# Phase_Voltage_Dividers.net
KiCad netlist of a schematic drawn in Altium Designer
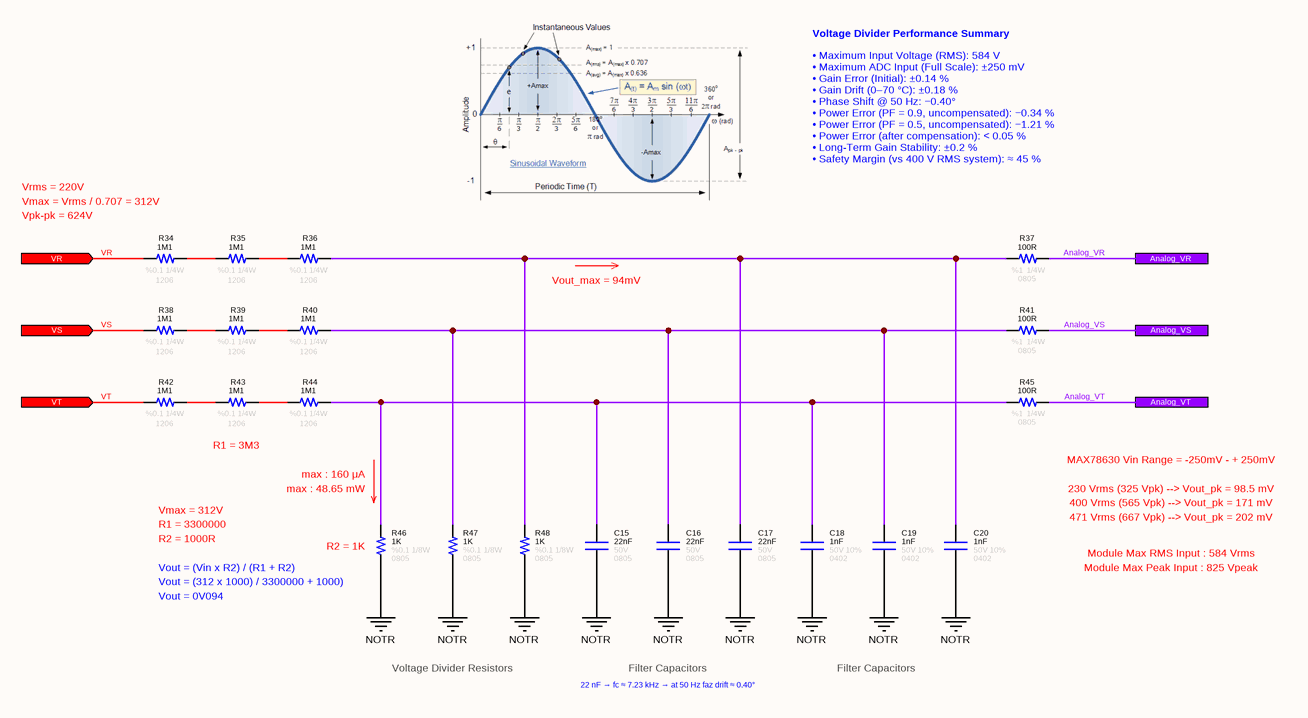
[diagram p0: Phase Voltage Dividers.SchDoc]

(export (version "E")
  (design (tool "Eeschema 10.0.6"))
  (components
    (comp (ref "C15")
      (value "22nF")
      (footprint "CAPACITOR_0805")
      (description "Capacitor (MLCC) - 22nF / 50V / 0805")
      (fields
        (field (name "MANUFACTURER PART NUMBER") "C0805C223K5RACTU")
        (field (name "TOLERANCE") "10%")
        (field (name "CASE") "0805")
        (field (name "VOLTAGE") "50V")
      )
      (libsource (lib "Akkoyun") (part "Capacitor - 22nF [0805-50V]"))
    )
    (comp (ref "C16")
      (value "22nF")
      (footprint "CAPACITOR_0805")
      (description "Capacitor (MLCC) - 22nF / 50V / 0805")
      (fields
        (field (name "MANUFACTURER PART NUMBER") "C0805C223K5RACTU")
        (field (name "TOLERANCE") "10%")
        (field (name "CASE") "0805")
        (field (name "VOLTAGE") "50V")
      )
      (libsource (lib "Akkoyun") (part "Capacitor - 22nF [0805-50V]"))
    )
    (comp (ref "C17")
      (value "22nF")
      (footprint "CAPACITOR_0805")
      (description "Capacitor (MLCC) - 22nF / 50V / 0805")
      (fields
        (field (name "MANUFACTURER PART NUMBER") "C0805C223K5RACTU")
        (field (name "TOLERANCE") "10%")
        (field (name "CASE") "0805")
        (field (name "VOLTAGE") "50V")
      )
      (libsource (lib "Akkoyun") (part "Capacitor - 22nF [0805-50V]"))
    )
    (comp (ref "C18")
      (value "1nF")
      (footprint "CAPACITOR_0402")
      (description "Capacitor (MLCC) - 1nF / 50V / 0402")
      (fields
        (field (name "MANUFACTURER PART NUMBER") "GRM155R71H102KA01D")
        (field (name "TOLERANCE") "10%")
        (field (name "CASE") "0402")
        (field (name "VOLTAGE") "50V")
        (field (name "Comment") "Capacitor - 1nF [0402] (MLCC)")
      )
      (libsource (lib "Akkoyun") (part "Capacitor - 1nF [0402-50V]"))
    )
    (comp (ref "C19")
      (value "1nF")
      (footprint "CAPACITOR_0402")
      (description "Capacitor (MLCC) - 1nF / 50V / 0402")
      (fields
        (field (name "MANUFACTURER PART NUMBER") "GRM155R71H102KA01D")
        (field (name "TOLERANCE") "10%")
        (field (name "CASE") "0402")
        (field (name "VOLTAGE") "50V")
        (field (name "Comment") "Capacitor - 1nF [0402] (MLCC)")
      )
      (libsource (lib "Akkoyun") (part "Capacitor - 1nF [0402-50V]"))
    )
    (comp (ref "C20")
      (value "1nF")
      (footprint "CAPACITOR_0402")
      (description "Capacitor (MLCC) - 1nF / 50V / 0402")
      (fields
        (field (name "MANUFACTURER PART NUMBER") "GRM155R71H102KA01D")
        (field (name "TOLERANCE") "10%")
        (field (name "CASE") "0402")
        (field (name "VOLTAGE") "50V")
        (field (name "Comment") "Capacitor - 1nF [0402] (MLCC)")
      )
      (libsource (lib "Akkoyun") (part "Capacitor - 1nF [0402-50V]"))
    )
    (comp (ref "R34")
      (value "1M1")
      (footprint "RESISTOR_1206")
      (description "Thick Film Resistors - SMD 1/4 W 1.1 MOhm 0.1%")
      (fields
        (field (name "MANUFACTURER PART NUMBER") "RT1206BRD071M1L")
        (field (name "CASE") "1206")
        (field (name "TOLERANCE") "%0.1")
        (field (name "POWER") "1/4W")
        (field (name "Comment") "1M1 - 1206 - %1 - 1/4W")
      )
      (libsource (lib "Akkoyun") (part "Resistor - 1M1 [1206] %0.1"))
    )
    (comp (ref "R35")
      (value "1M1")
      (footprint "RESISTOR_1206")
      (description "Thick Film Resistors - SMD 1/4 W 1.1 MOhm 0.1%")
      (fields
        (field (name "MANUFACTURER PART NUMBER") "RT1206BRD071M1L")
        (field (name "CASE") "1206")
        (field (name "TOLERANCE") "%0.1")
        (field (name "POWER") "1/4W")
        (field (name "Comment") "1M1 - 1206 - %1 - 1/4W")
      )
      (libsource (lib "Akkoyun") (part "Resistor - 1M1 [1206] %0.1"))
    )
    (comp (ref "R36")
      (value "1M1")
      (footprint "RESISTOR_1206")
      (description "Thick Film Resistors - SMD 1/4 W 1.1 MOhm 0.1%")
      (fields
        (field (name "MANUFACTURER PART NUMBER") "RT1206BRD071M1L")
        (field (name "CASE") "1206")
        (field (name "TOLERANCE") "%0.1")
        (field (name "POWER") "1/4W")
        (field (name "Comment") "1M1 - 1206 - %1 - 1/4W")
      )
      (libsource (lib "Akkoyun") (part "Resistor - 1M1 [1206] %0.1"))
    )
    (comp (ref "R37")
      (value "100R")
      (footprint "RESISTOR_0805")
      (description "Thick Film Resistors - SMD 1/4 W 100 Ohm 1%")
      (fields
        (field (name "MANUFACTURER PART NUMBER") "CRCW0805100RFKEA")
        (field (name "CASE") "0805")
        (field (name "TOLERANCE") "%1")
        (field (name "POWER") "1/4W")
        (field (name "Comment") "100R - 0805 - %1 - 1/4W")
      )
      (libsource (lib "Akkoyun") (part "Resistor - 100R [0805]"))
    )
    (comp (ref "R38")
      (value "1M1")
      (footprint "RESISTOR_1206")
      (description "Thick Film Resistors - SMD 1/4 W 1.1 MOhm 0.1%")
      (fields
        (field (name "MANUFACTURER PART NUMBER") "RT1206BRD071M1L")
        (field (name "CASE") "1206")
        (field (name "TOLERANCE") "%0.1")
        (field (name "POWER") "1/4W")
        (field (name "Comment") "1M1 - 1206 - %1 - 1/4W")
      )
      (libsource (lib "Akkoyun") (part "Resistor - 1M1 [1206] %0.1"))
    )
    (comp (ref "R39")
      (value "1M1")
      (footprint "RESISTOR_1206")
      (description "Thick Film Resistors - SMD 1/4 W 1.1 MOhm 0.1%")
      (fields
        (field (name "MANUFACTURER PART NUMBER") "RT1206BRD071M1L")
        (field (name "CASE") "1206")
        (field (name "TOLERANCE") "%0.1")
        (field (name "POWER") "1/4W")
        (field (name "Comment") "1M1 - 1206 - %1 - 1/4W")
      )
      (libsource (lib "Akkoyun") (part "Resistor - 1M1 [1206] %0.1"))
    )
    (comp (ref "R40")
      (value "1M1")
      (footprint "RESISTOR_1206")
      (description "Thick Film Resistors - SMD 1/4 W 1.1 MOhm 0.1%")
      (fields
        (field (name "MANUFACTURER PART NUMBER") "RT1206BRD071M1L")
        (field (name "CASE") "1206")
        (field (name "TOLERANCE") "%0.1")
        (field (name "POWER") "1/4W")
        (field (name "Comment") "1M1 - 1206 - %1 - 1/4W")
      )
      (libsource (lib "Akkoyun") (part "Resistor - 1M1 [1206] %0.1"))
    )
    (comp (ref "R41")
      (value "100R")
      (footprint "RESISTOR_0805")
      (description "Thick Film Resistors - SMD 1/4 W 100 Ohm 1%")
      (fields
        (field (name "MANUFACTURER PART NUMBER") "CRCW0805100RFKEA")
        (field (name "CASE") "0805")
        (field (name "TOLERANCE") "%1")
        (field (name "POWER") "1/4W")
        (field (name "Comment") "100R - 0805 - %1 - 1/4W")
      )
      (libsource (lib "Akkoyun") (part "Resistor - 100R [0805]"))
    )
    (comp (ref "R42")
      (value "1M1")
      (footprint "RESISTOR_1206")
      (description "Thick Film Resistors - SMD 1/4 W 1.1 MOhm 0.1%")
      (fields
        (field (name "MANUFACTURER PART NUMBER") "RT1206BRD071M1L")
        (field (name "CASE") "1206")
        (field (name "TOLERANCE") "%0.1")
        (field (name "POWER") "1/4W")
        (field (name "Comment") "1M1 - 1206 - %1 - 1/4W")
      )
      (libsource (lib "Akkoyun") (part "Resistor - 1M1 [1206] %0.1"))
    )
    (comp (ref "R43")
      (value "1M1")
      (footprint "RESISTOR_1206")
      (description "Thick Film Resistors - SMD 1/4 W 1.1 MOhm 0.1%")
      (fields
        (field (name "MANUFACTURER PART NUMBER") "RT1206BRD071M1L")
        (field (name "CASE") "1206")
        (field (name "TOLERANCE") "%0.1")
        (field (name "POWER") "1/4W")
        (field (name "Comment") "1M1 - 1206 - %1 - 1/4W")
      )
      (libsource (lib "Akkoyun") (part "Resistor - 1M1 [1206] %0.1"))
    )
    (comp (ref "R44")
      (value "1M1")
      (footprint "RESISTOR_1206")
      (description "Thick Film Resistors - SMD 1/4 W 1.1 MOhm 0.1%")
      (fields
        (field (name "MANUFACTURER PART NUMBER") "RT1206BRD071M1L")
        (field (name "CASE") "1206")
        (field (name "TOLERANCE") "%0.1")
        (field (name "POWER") "1/4W")
        (field (name "Comment") "1M1 - 1206 - %1 - 1/4W")
      )
      (libsource (lib "Akkoyun") (part "Resistor - 1M1 [1206] %0.1"))
    )
    (comp (ref "R45")
      (value "100R")
      (footprint "RESISTOR_0805")
      (description "Thick Film Resistors - SMD 1/4 W 100 Ohm 1%")
      (fields
        (field (name "MANUFACTURER PART NUMBER") "CRCW0805100RFKEA")
        (field (name "CASE") "0805")
        (field (name "TOLERANCE") "%1")
        (field (name "POWER") "1/4W")
        (field (name "Comment") "100R - 0805 - %1 - 1/4W")
      )
      (libsource (lib "Akkoyun") (part "Resistor - 100R [0805]"))
    )
    (comp (ref "R46")
      (value "1K")
      (footprint "RESISTOR_0805")
      (description "Thick Film Resistors - SMD 1/8 W 1 KOhm 0.1%")
      (fields
        (field (name "MANUFACTURER PART NUMBER") "ERA-6AEB102V")
        (field (name "TOLERANCE") "%0.1")
        (field (name "CASE") "0805")
        (field (name "POWER") "1/8W")
        (field (name "Comment") "1K - 0805 - %0.1 - 1/8W")
      )
      (libsource (lib "Akkoyun") (part "Resistor - 1K [0805]"))
    )
    (comp (ref "R47")
      (value "1K")
      (footprint "RESISTOR_0805")
      (description "Thick Film Resistors - SMD 1/8 W 1 KOhm 0.1%")
      (fields
        (field (name "MANUFACTURER PART NUMBER") "ERA-6AEB102V")
        (field (name "TOLERANCE") "%0.1")
        (field (name "CASE") "0805")
        (field (name "POWER") "1/8W")
        (field (name "Comment") "1K - 0805 - %0.1 - 1/8W")
      )
      (libsource (lib "Akkoyun") (part "Resistor - 1K [0805]"))
    )
    (comp (ref "R48")
      (value "1K")
      (footprint "RESISTOR_0805")
      (description "Thick Film Resistors - SMD 1/8 W 1 KOhm 0.1%")
      (fields
        (field (name "MANUFACTURER PART NUMBER") "ERA-6AEB102V")
        (field (name "TOLERANCE") "%0.1")
        (field (name "CASE") "0805")
        (field (name "POWER") "1/8W")
        (field (name "Comment") "1K - 0805 - %0.1 - 1/8W")
      )
      (libsource (lib "Akkoyun") (part "Resistor - 1K [0805]"))
    )
  )
  (nets
    (net (code "1") (name "/Analog_VR") (class "Default")
      (node (ref "R37") (pin "1") (pinfunction "1_1") (pintype "passive"))
    )
    (net (code "2") (name "/Analog_VS") (class "Default")
      (node (ref "R41") (pin "1") (pinfunction "1_1") (pintype "passive"))
    )
    (net (code "3") (name "/Analog_VT") (class "Default")
      (node (ref "R45") (pin "1") (pinfunction "1_1") (pintype "passive"))
    )
    (net (code "4") (name "/VR") (class "Default")
      (node (ref "R34") (pin "2") (pinfunction "2_2") (pintype "passive"))
    )
    (net (code "5") (name "/VS") (class "Default")
      (node (ref "R38") (pin "2") (pinfunction "2_2") (pintype "passive"))
    )
    (net (code "6") (name "/VT") (class "Default")
      (node (ref "R42") (pin "2") (pinfunction "2_2") (pintype "passive"))
    )
    (net (code "7") (name "NOTR") (class "Default")
      (node (ref "C15") (pin "1") (pinfunction "1_1") (pintype "passive"))
      (node (ref "C16") (pin "1") (pinfunction "1_1") (pintype "passive"))
      (node (ref "C17") (pin "1") (pinfunction "1_1") (pintype "passive"))
      (node (ref "C18") (pin "1") (pinfunction "1_1") (pintype "passive"))
      (node (ref "C19") (pin "1") (pinfunction "1_1") (pintype "passive"))
      (node (ref "C20") (pin "1") (pinfunction "1_1") (pintype "passive"))
      (node (ref "R46") (pin "1") (pinfunction "1_1") (pintype "passive"))
      (node (ref "R47") (pin "1") (pinfunction "1_1") (pintype "passive"))
      (node (ref "R48") (pin "1") (pinfunction "1_1") (pintype "passive"))
    )
    (net (code "8") (name "Net-(C15-Pad2)") (class "Default")
      (node (ref "C15") (pin "2") (pinfunction "2_2") (pintype "passive"))
      (node (ref "C18") (pin "2") (pinfunction "2_2") (pintype "passive"))
      (node (ref "R44") (pin "1") (pinfunction "1_1") (pintype "passive"))
      (node (ref "R45") (pin "2") (pinfunction "2_2") (pintype "passive"))
      (node (ref "R46") (pin "2") (pinfunction "2_2") (pintype "passive"))
    )
    (net (code "9") (name "Net-(C16-Pad2)") (class "Default")
      (node (ref "C16") (pin "2") (pinfunction "2_2") (pintype "passive"))
      (node (ref "C19") (pin "2") (pinfunction "2_2") (pintype "passive"))
      (node (ref "R40") (pin "1") (pinfunction "1_1") (pintype "passive"))
      (node (ref "R41") (pin "2") (pinfunction "2_2") (pintype "passive"))
      (node (ref "R47") (pin "2") (pinfunction "2_2") (pintype "passive"))
    )
    (net (code "10") (name "Net-(C17-Pad2)") (class "Default")
      (node (ref "C17") (pin "2") (pinfunction "2_2") (pintype "passive"))
      (node (ref "C20") (pin "2") (pinfunction "2_2") (pintype "passive"))
      (node (ref "R36") (pin "1") (pinfunction "1_1") (pintype "passive"))
      (node (ref "R37") (pin "2") (pinfunction "2_2") (pintype "passive"))
      (node (ref "R48") (pin "2") (pinfunction "2_2") (pintype "passive"))
    )
    (net (code "11") (name "Net-(R34-Pad1)") (class "Default")
      (node (ref "R34") (pin "1") (pinfunction "1_1") (pintype "passive"))
      (node (ref "R35") (pin "2") (pinfunction "2_2") (pintype "passive"))
    )
    (net (code "12") (name "Net-(R35-Pad1)") (class "Default")
      (node (ref "R35") (pin "1") (pinfunction "1_1") (pintype "passive"))
      (node (ref "R36") (pin "2") (pinfunction "2_2") (pintype "passive"))
    )
    (net (code "13") (name "Net-(R38-Pad1)") (class "Default")
      (node (ref "R38") (pin "1") (pinfunction "1_1") (pintype "passive"))
      (node (ref "R39") (pin "2") (pinfunction "2_2") (pintype "passive"))
    )
    (net (code "14") (name "Net-(R39-Pad1)") (class "Default")
      (node (ref "R39") (pin "1") (pinfunction "1_1") (pintype "passive"))
      (node (ref "R40") (pin "2") (pinfunction "2_2") (pintype "passive"))
    )
    (net (code "15") (name "Net-(R42-Pad1)") (class "Default")
      (node (ref "R42") (pin "1") (pinfunction "1_1") (pintype "passive"))
      (node (ref "R43") (pin "2") (pinfunction "2_2") (pintype "passive"))
    )
    (net (code "16") (name "Net-(R43-Pad1)") (class "Default")
      (node (ref "R43") (pin "1") (pinfunction "1_1") (pintype "passive"))
      (node (ref "R44") (pin "2") (pinfunction "2_2") (pintype "passive"))
    )
  )
)
